# AUX_CPU_SCH.net
KiCad netlist of a schematic drawn in Altium Designer
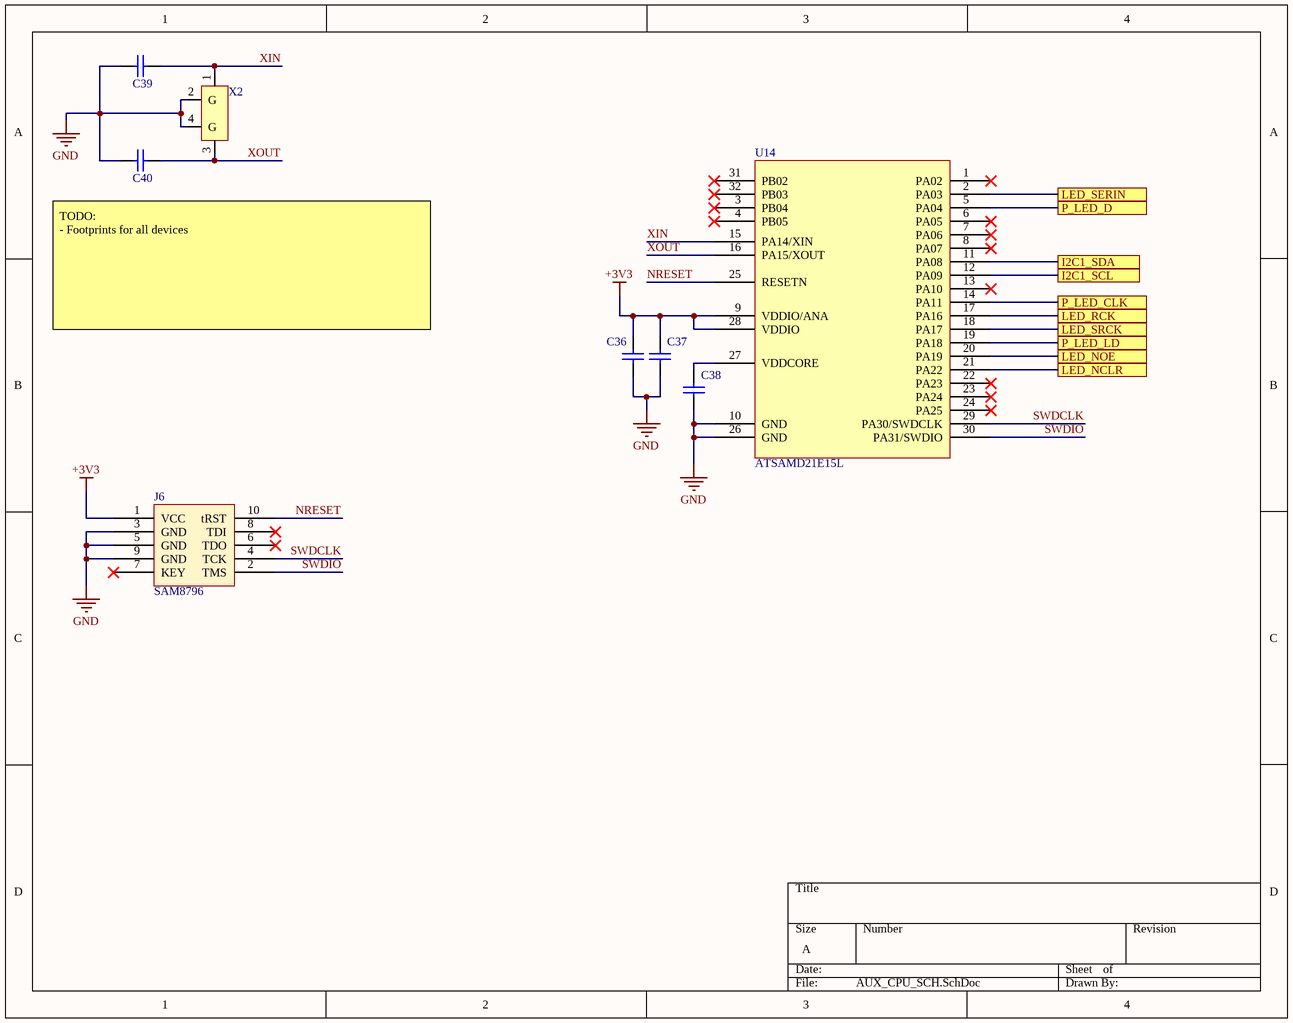
[diagram p0: AUX_CPU_SCH.SchDoc]

(export (version "E")
  (design (tool "Eeschema 10.0.6"))
  (components
    (comp (ref "C36")
      (value "CAP0402")
      (footprint "CAPC0402(1005)60_L")
      (description "0402 (1005 Metric) Chip Capacitor")
      (libsource (lib "Altium Content Vault") (part "CAP_5"))
    )
    (comp (ref "C37")
      (value "CAP0402")
      (footprint "CAPC0402(1005)60_L")
      (description "0402 (1005 Metric) Chip Capacitor")
      (libsource (lib "Altium Content Vault") (part "CAP_5"))
    )
    (comp (ref "C38")
      (value "CAP0402")
      (footprint "CAPC0402(1005)60_L")
      (description "0402 (1005 Metric) Chip Capacitor")
      (libsource (lib "Altium Content Vault") (part "CAP_5"))
    )
    (comp (ref "C39")
      (value "CAP0402")
      (footprint "CAPC0402(1005)60_L")
      (description "0402 (1005 Metric) Chip Capacitor")
      (libsource (lib "Altium Content Vault") (part "CAP_5"))
    )
    (comp (ref "C40")
      (value "CAP0402")
      (footprint "CAPC0402(1005)60_L")
      (description "0402 (1005 Metric) Chip Capacitor")
      (libsource (lib "Altium Content Vault") (part "CAP_5"))
    )
    (comp (ref "J6") (value "SAM8796") (libsource (lib "Copter") (part "SAM8796")))
    (comp (ref "U14") (value "ATSAMD21E15L") (libsource (lib "Copter") (part "ATSAMD21E15L")))
    (comp (ref "X2")
      (value "ECS-480-18-30B-AGN-TR")
      (libsource (lib "Copter") (part "ECS-480-18-30B-AGN-TR"))
    )
  )
  (nets
    (net (code "1") (name "+3V3") (class "Default")
      (node (ref "C36") (pin "2") (pinfunction "2_2") (pintype "passive"))
      (node (ref "C37") (pin "2") (pinfunction "2_2") (pintype "passive"))
      (node (ref "J6") (pin "1") (pinfunction "VCC_1") (pintype "passive"))
      (node (ref "U14") (pin "28") (pinfunction "VDDIO_28") (pintype "passive"))
      (node (ref "U14") (pin "9") (pinfunction "VDDIO/ANA_9") (pintype "passive"))
    )
    (net (code "2") (name "/I2C1_SCL") (class "Default")
      (node (ref "U14") (pin "12") (pinfunction "PA09_12") (pintype "passive"))
    )
    (net (code "3") (name "/I2C1_SDA") (class "Default")
      (node (ref "U14") (pin "11") (pinfunction "PA08_11") (pintype "passive"))
    )
    (net (code "4") (name "/LED_NCLR") (class "Default")
      (node (ref "U14") (pin "21") (pinfunction "PA22_21") (pintype "passive"))
    )
    (net (code "5") (name "/LED_NOE") (class "Default")
      (node (ref "U14") (pin "20") (pinfunction "PA19_20") (pintype "passive"))
    )
    (net (code "6") (name "/LED_RCK") (class "Default")
      (node (ref "U14") (pin "17") (pinfunction "PA16_17") (pintype "passive"))
    )
    (net (code "7") (name "/LED_SERIN") (class "Default")
      (node (ref "U14") (pin "2") (pinfunction "PA03_2") (pintype "passive"))
    )
    (net (code "8") (name "/LED_SRCK") (class "Default")
      (node (ref "U14") (pin "18") (pinfunction "PA17_18") (pintype "passive"))
    )
    (net (code "9") (name "/NRESET") (class "Default")
      (node (ref "J6") (pin "10") (pinfunction "tRST_10") (pintype "passive"))
      (node (ref "U14") (pin "25") (pinfunction "RESETN_25") (pintype "passive"))
    )
    (net (code "10") (name "/P_LED_CLK") (class "Default")
      (node (ref "U14") (pin "14") (pinfunction "PA11_14") (pintype "passive"))
    )
    (net (code "11") (name "/P_LED_D") (class "Default")
      (node (ref "U14") (pin "5") (pinfunction "PA04_5") (pintype "passive"))
    )
    (net (code "12") (name "/P_LED_LD") (class "Default")
      (node (ref "U14") (pin "19") (pinfunction "PA18_19") (pintype "passive"))
    )
    (net (code "13") (name "/SWDCLK") (class "Default")
      (node (ref "J6") (pin "4") (pinfunction "TCK_4") (pintype "passive"))
      (node (ref "U14") (pin "29") (pinfunction "PA30/SWDCLK_29") (pintype "passive"))
    )
    (net (code "14") (name "/SWDIO") (class "Default")
      (node (ref "J6") (pin "2") (pinfunction "TMS_2") (pintype "passive"))
      (node (ref "U14") (pin "30") (pinfunction "PA31/SWDIO_30") (pintype "passive"))
    )
    (net (code "15") (name "/XIN") (class "Default")
      (node (ref "C39") (pin "1") (pinfunction "1_1") (pintype "passive"))
      (node (ref "U14") (pin "15") (pinfunction "PA14/XIN_15") (pintype "passive"))
      (node (ref "X2") (pin "1") (pinfunction "XIN_1") (pintype "passive"))
    )
    (net (code "16") (name "/XOUT") (class "Default")
      (node (ref "C40") (pin "1") (pinfunction "1_1") (pintype "passive"))
      (node (ref "U14") (pin "16") (pinfunction "PA15/XOUT_16") (pintype "passive"))
      (node (ref "X2") (pin "3") (pinfunction "XOUT_3") (pintype "passive"))
    )
    (net (code "17") (name "GND") (class "Default")
      (node (ref "C36") (pin "1") (pinfunction "1_1") (pintype "passive"))
      (node (ref "C37") (pin "1") (pinfunction "1_1") (pintype "passive"))
      (node (ref "C38") (pin "1") (pinfunction "1_1") (pintype "passive"))
      (node (ref "C39") (pin "2") (pinfunction "2_2") (pintype "passive"))
      (node (ref "C40") (pin "2") (pinfunction "2_2") (pintype "passive"))
      (node (ref "J6") (pin "3") (pinfunction "GND_3") (pintype "passive"))
      (node (ref "J6") (pin "5") (pinfunction "GND_5") (pintype "passive"))
      (node (ref "J6") (pin "9") (pinfunction "GND_9") (pintype "passive"))
      (node (ref "U14") (pin "10") (pinfunction "GND_10") (pintype "passive"))
      (node (ref "U14") (pin "26") (pinfunction "GND_26") (pintype "passive"))
      (node (ref "X2") (pin "2") (pinfunction "G_2") (pintype "passive"))
      (node (ref "X2") (pin "4") (pinfunction "G_4") (pintype "passive"))
    )
    (net (code "18") (name "Net-(U14-VDDCORE)") (class "Default")
      (node (ref "C38") (pin "2") (pinfunction "2_2") (pintype "passive"))
      (node (ref "U14") (pin "27") (pinfunction "VDDCORE_27") (pintype "passive"))
    )
    (net (code "19") (name "unconnected-(J6-KEY-Pad7)") (class "Default")
      (node (ref "J6") (pin "7") (pinfunction "KEY_7") (pintype "passive+no_connect"))
    )
    (net (code "20") (name "unconnected-(J6-TDI-Pad8)") (class "Default")
      (node (ref "J6") (pin "8") (pinfunction "TDI_8") (pintype "passive+no_connect"))
    )
    (net (code "21") (name "unconnected-(J6-TDO-Pad6)") (class "Default")
      (node (ref "J6") (pin "6") (pinfunction "TDO_6") (pintype "passive+no_connect"))
    )
    (net (code "22") (name "unconnected-(U14-PA02-Pad1)") (class "Default")
      (node (ref "U14") (pin "1") (pinfunction "PA02_1") (pintype "passive+no_connect"))
    )
    (net (code "23") (name "unconnected-(U14-PA05-Pad6)") (class "Default")
      (node (ref "U14") (pin "6") (pinfunction "PA05_6") (pintype "passive+no_connect"))
    )
    (net (code "24") (name "unconnected-(U14-PA06-Pad7)") (class "Default")
      (node (ref "U14") (pin "7") (pinfunction "PA06_7") (pintype "passive+no_connect"))
    )
    (net (code "25") (name "unconnected-(U14-PA07-Pad8)") (class "Default")
      (node (ref "U14") (pin "8") (pinfunction "PA07_8") (pintype "passive+no_connect"))
    )
    (net (code "26") (name "unconnected-(U14-PA10-Pad13)") (class "Default")
      (node (ref "U14") (pin "13") (pinfunction "PA10_13") (pintype "passive+no_connect"))
    )
    (net (code "27") (name "unconnected-(U14-PA23-Pad22)") (class "Default")
      (node (ref "U14") (pin "22") (pinfunction "PA23_22") (pintype "passive+no_connect"))
    )
    (net (code "28") (name "unconnected-(U14-PA24-Pad23)") (class "Default")
      (node (ref "U14") (pin "23") (pinfunction "PA24_23") (pintype "passive+no_connect"))
    )
    (net (code "29") (name "unconnected-(U14-PA25-Pad24)") (class "Default")
      (node (ref "U14") (pin "24") (pinfunction "PA25_24") (pintype "passive+no_connect"))
    )
    (net (code "30") (name "unconnected-(U14-PB02-Pad31)") (class "Default")
      (node (ref "U14") (pin "31") (pinfunction "PB02_31") (pintype "passive+no_connect"))
    )
    (net (code "31") (name "unconnected-(U14-PB03-Pad32)") (class "Default")
      (node (ref "U14") (pin "32") (pinfunction "PB03_32") (pintype "passive+no_connect"))
    )
    (net (code "32") (name "unconnected-(U14-PB04-Pad3)") (class "Default")
      (node (ref "U14") (pin "3") (pinfunction "PB04_3") (pintype "passive+no_connect"))
    )
    (net (code "33") (name "unconnected-(U14-PB05-Pad4)") (class "Default")
      (node (ref "U14") (pin "4") (pinfunction "PB05_4") (pintype "passive+no_connect"))
    )
  )
)
